# INC_ENC_IF.net
KiCad netlist of a schematic drawn in Altium Designer
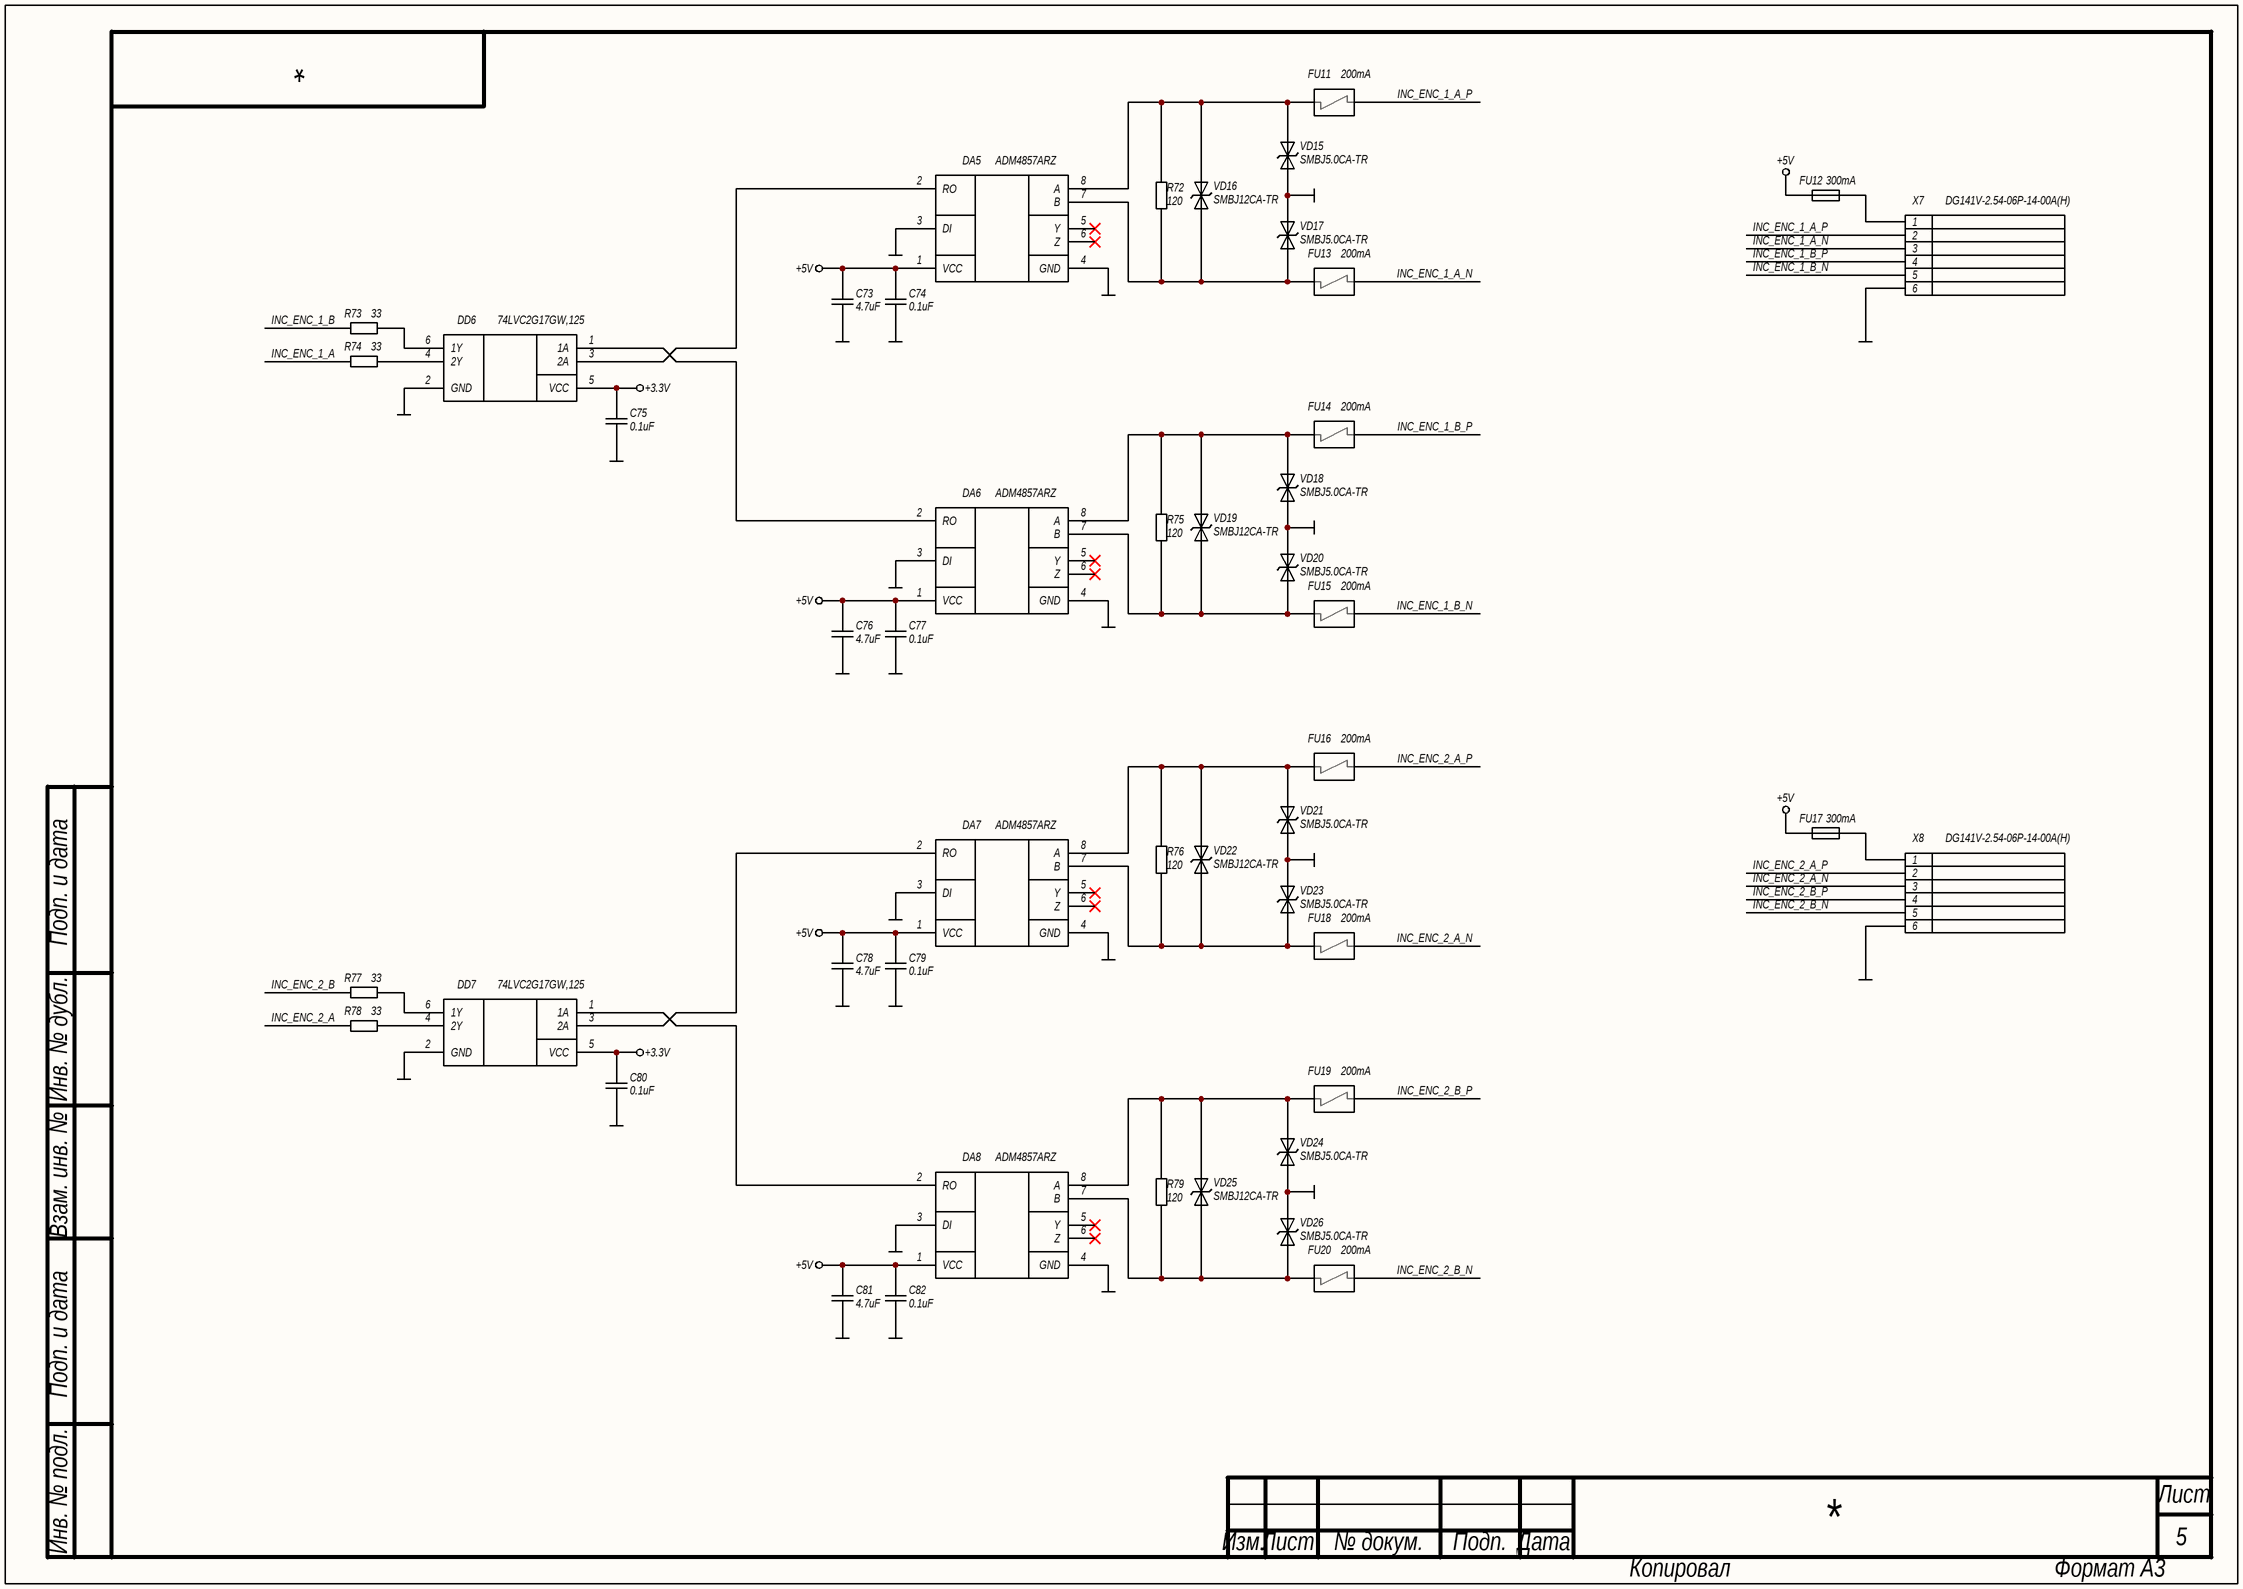
[diagram p0: INC_ENC_IF.SchDoc]

(export (version "E")
  (design (tool "Eeschema 10.0.6"))
  (components
    (comp (ref "C73")
      (value "4.7uF")
      (footprint "C0603N")
      (description "Конденсатор")
      (libsource (lib "Components Library") (part "CAP_FIXED"))
    )
    (comp (ref "C74")
      (value "0.1uF")
      (footprint "C0603N")
      (description "Конденсатор")
      (libsource (lib "Components Library") (part "CAP_FIXED"))
    )
    (comp (ref "C75")
      (value "0.1uF")
      (footprint "C0603N")
      (description "Конденсатор")
      (libsource (lib "Components Library") (part "CAP_FIXED"))
    )
    (comp (ref "C76")
      (value "4.7uF")
      (footprint "C0603N")
      (description "Конденсатор")
      (libsource (lib "Components Library") (part "CAP_FIXED"))
    )
    (comp (ref "C77")
      (value "0.1uF")
      (footprint "C0603N")
      (description "Конденсатор")
      (libsource (lib "Components Library") (part "CAP_FIXED"))
    )
    (comp (ref "C78")
      (value "4.7uF")
      (footprint "C0603N")
      (description "Конденсатор")
      (libsource (lib "Components Library") (part "CAP_FIXED"))
    )
    (comp (ref "C79")
      (value "0.1uF")
      (footprint "C0603N")
      (description "Конденсатор")
      (libsource (lib "Components Library") (part "CAP_FIXED"))
    )
    (comp (ref "C80")
      (value "0.1uF")
      (footprint "C0603N")
      (description "Конденсатор")
      (libsource (lib "Components Library") (part "CAP_FIXED"))
    )
    (comp (ref "C81")
      (value "4.7uF")
      (footprint "C0603N")
      (description "Конденсатор")
      (libsource (lib "Components Library") (part "CAP_FIXED"))
    )
    (comp (ref "C82")
      (value "0.1uF")
      (footprint "C0603N")
      (description "Конденсатор")
      (libsource (lib "Components Library") (part "CAP_FIXED"))
    )
    (comp (ref "DA5")
      (value "ADM4857ARZ")
      (footprint "SOIC8")
      (description "Микросхема интерфейса RS485")
      (libsource (lib "Components Library") (part "ADM4857A"))
    )
    (comp (ref "DA6")
      (value "ADM4857ARZ")
      (footprint "SOIC8")
      (description "Микросхема интерфейса RS485")
      (libsource (lib "Components Library") (part "ADM4857A"))
    )
    (comp (ref "DA7")
      (value "ADM4857ARZ")
      (footprint "SOIC8")
      (description "Микросхема интерфейса RS485")
      (libsource (lib "Components Library") (part "ADM4857A"))
    )
    (comp (ref "DA8")
      (value "ADM4857ARZ")
      (footprint "SOIC8")
      (description "Микросхема интерфейса RS485")
      (libsource (lib "Components Library") (part "ADM4857A"))
    )
    (comp (ref "DD6")
      (value "74LVC2G17GW,125")
      (footprint "SOT363-2")
      (description "Микросхема сдвоенный триггер Шмитта")
      (libsource (lib "Components Library") (part "74LVC2G17"))
    )
    (comp (ref "DD7")
      (value "74LVC2G17GW,125")
      (footprint "SOT363-2")
      (description "Микросхема сдвоенный триггер Шмитта")
      (libsource (lib "Components Library") (part "74LVC2G17"))
    )
    (comp (ref "FU11")
      (value "200mA")
      (footprint "TBU-CA")
      (description "Полупроводниковый предохранитель")
      (libsource (lib "Components Library") (part "FUSE_TBU"))
    )
    (comp (ref "FU12")
      (value "300mA")
      (footprint "MF-MSMF")
      (description "Плавкий предохранитель")
      (libsource (lib "Components Library") (part "FUSE"))
    )
    (comp (ref "FU13")
      (value "200mA")
      (footprint "TBU-CA")
      (description "Полупроводниковый предохранитель")
      (libsource (lib "Components Library") (part "FUSE_TBU"))
    )
    (comp (ref "FU14")
      (value "200mA")
      (footprint "TBU-CA")
      (description "Полупроводниковый предохранитель")
      (libsource (lib "Components Library") (part "FUSE_TBU"))
    )
    (comp (ref "FU15")
      (value "200mA")
      (footprint "TBU-CA")
      (description "Полупроводниковый предохранитель")
      (libsource (lib "Components Library") (part "FUSE_TBU"))
    )
    (comp (ref "FU16")
      (value "200mA")
      (footprint "TBU-CA")
      (description "Полупроводниковый предохранитель")
      (libsource (lib "Components Library") (part "FUSE_TBU"))
    )
    (comp (ref "FU17")
      (value "300mA")
      (footprint "MF-MSMF")
      (description "Плавкий предохранитель")
      (libsource (lib "Components Library") (part "FUSE"))
    )
    (comp (ref "FU18")
      (value "200mA")
      (footprint "TBU-CA")
      (description "Полупроводниковый предохранитель")
      (libsource (lib "Components Library") (part "FUSE_TBU"))
    )
    (comp (ref "FU19")
      (value "200mA")
      (footprint "TBU-CA")
      (description "Полупроводниковый предохранитель")
      (libsource (lib "Components Library") (part "FUSE_TBU"))
    )
    (comp (ref "FU20")
      (value "200mA")
      (footprint "TBU-CA")
      (description "Полупроводниковый предохранитель")
      (libsource (lib "Components Library") (part "FUSE_TBU"))
    )
    (comp (ref "R72")
      (value "120")
      (footprint "R0805N")
      (description "Резистор")
      (libsource (lib "") (part "RES_FIXED_1"))
    )
    (comp (ref "R73")
      (value "33")
      (footprint "R0603N")
      (description "Резистор")
      (libsource (lib "Components Library") (part "RES_FIXED"))
    )
    (comp (ref "R74")
      (value "33")
      (footprint "R0603N")
      (description "Резистор")
      (libsource (lib "Components Library") (part "RES_FIXED"))
    )
    (comp (ref "R75")
      (value "120")
      (footprint "R0805N")
      (description "Резистор")
      (libsource (lib "") (part "RES_FIXED_1"))
    )
    (comp (ref "R76")
      (value "120")
      (footprint "R0805N")
      (description "Резистор")
      (libsource (lib "") (part "RES_FIXED_1"))
    )
    (comp (ref "R77")
      (value "33")
      (footprint "R0603N")
      (description "Резистор")
      (libsource (lib "Components Library") (part "RES_FIXED"))
    )
    (comp (ref "R78")
      (value "33")
      (footprint "R0603N")
      (description "Резистор")
      (libsource (lib "Components Library") (part "RES_FIXED"))
    )
    (comp (ref "R79")
      (value "120")
      (footprint "R0805N")
      (description "Резистор")
      (libsource (lib "") (part "RES_FIXED_1"))
    )
    (comp (ref "VD15")
      (value "SMBJ5.0CA-TR")
      (footprint "SMB")
      (description "TVS диод двунаправленный")
      (libsource (lib "Components Library") (part "TVS_BIDIR"))
    )
    (comp (ref "VD16")
      (value "SMBJ12CA-TR")
      (footprint "SMB")
      (description "TVS диод двунаправленный")
      (libsource (lib "Components Library") (part "TVS_BIDIR"))
    )
    (comp (ref "VD17")
      (value "SMBJ5.0CA-TR")
      (footprint "SMB")
      (description "TVS диод двунаправленный")
      (libsource (lib "Components Library") (part "TVS_BIDIR"))
    )
    (comp (ref "VD18")
      (value "SMBJ5.0CA-TR")
      (footprint "SMB")
      (description "TVS диод двунаправленный")
      (libsource (lib "Components Library") (part "TVS_BIDIR"))
    )
    (comp (ref "VD19")
      (value "SMBJ12CA-TR")
      (footprint "SMB")
      (description "TVS диод двунаправленный")
      (libsource (lib "Components Library") (part "TVS_BIDIR"))
    )
    (comp (ref "VD20")
      (value "SMBJ5.0CA-TR")
      (footprint "SMB")
      (description "TVS диод двунаправленный")
      (libsource (lib "Components Library") (part "TVS_BIDIR"))
    )
    (comp (ref "VD21")
      (value "SMBJ5.0CA-TR")
      (footprint "SMB")
      (description "TVS диод двунаправленный")
      (libsource (lib "Components Library") (part "TVS_BIDIR"))
    )
    (comp (ref "VD22")
      (value "SMBJ12CA-TR")
      (footprint "SMB")
      (description "TVS диод двунаправленный")
      (libsource (lib "Components Library") (part "TVS_BIDIR"))
    )
    (comp (ref "VD23")
      (value "SMBJ5.0CA-TR")
      (footprint "SMB")
      (description "TVS диод двунаправленный")
      (libsource (lib "Components Library") (part "TVS_BIDIR"))
    )
    (comp (ref "VD24")
      (value "SMBJ5.0CA-TR")
      (footprint "SMB")
      (description "TVS диод двунаправленный")
      (libsource (lib "Components Library") (part "TVS_BIDIR"))
    )
    (comp (ref "VD25")
      (value "SMBJ12CA-TR")
      (footprint "SMB")
      (description "TVS диод двунаправленный")
      (libsource (lib "Components Library") (part "TVS_BIDIR"))
    )
    (comp (ref "VD26")
      (value "SMBJ5.0CA-TR")
      (footprint "SMB")
      (description "TVS диод двунаправленный")
      (libsource (lib "Components Library") (part "TVS_BIDIR"))
    )
    (comp (ref "X7")
      (value "DG141V-2.54-06P-14-00A(H)")
      (footprint "DG141V-2.54-06P-14-00A(H)")
      (description "Разъем, 6 контактов")
      (libsource (lib "Components Library") (part "Connector 6"))
    )
    (comp (ref "X8")
      (value "DG141V-2.54-06P-14-00A(H)")
      (footprint "DG141V-2.54-06P-14-00A(H)")
      (description "Разъем, 6 контактов")
      (libsource (lib "Components Library") (part "Connector 6"))
    )
  )
  (nets
    (net (code "1") (name "+3.3V") (class "Default")
      (node (ref "C75") (pin "2") (pinfunction "2_2") (pintype "passive"))
      (node (ref "C80") (pin "2") (pinfunction "2_2") (pintype "passive"))
      (node (ref "DD6") (pin "5") (pinfunction "VCC_5") (pintype "power_in"))
      (node (ref "DD7") (pin "5") (pinfunction "VCC_5") (pintype "power_in"))
    )
    (net (code "2") (name "+5V") (class "Default")
      (node (ref "C73") (pin "2") (pinfunction "2_2") (pintype "passive"))
      (node (ref "C74") (pin "2") (pinfunction "2_2") (pintype "passive"))
      (node (ref "C76") (pin "2") (pinfunction "2_2") (pintype "passive"))
      (node (ref "C77") (pin "2") (pinfunction "2_2") (pintype "passive"))
      (node (ref "C78") (pin "2") (pinfunction "2_2") (pintype "passive"))
      (node (ref "C79") (pin "2") (pinfunction "2_2") (pintype "passive"))
      (node (ref "C81") (pin "2") (pinfunction "2_2") (pintype "passive"))
      (node (ref "C82") (pin "2") (pinfunction "2_2") (pintype "passive"))
      (node (ref "DA5") (pin "1") (pinfunction "VCC_1") (pintype "power_in"))
      (node (ref "DA6") (pin "1") (pinfunction "VCC_1") (pintype "power_in"))
      (node (ref "DA7") (pin "1") (pinfunction "VCC_1") (pintype "power_in"))
      (node (ref "DA8") (pin "1") (pinfunction "VCC_1") (pintype "power_in"))
      (node (ref "FU12") (pin "1") (pinfunction "1_1") (pintype "passive"))
      (node (ref "FU17") (pin "1") (pinfunction "1_1") (pintype "passive"))
    )
    (net (code "3") (name "/INC_ENC_1_A") (class "Default")
      (node (ref "R74") (pin "2") (pinfunction "2_2") (pintype "passive"))
    )
    (net (code "4") (name "/INC_ENC_1_A_N") (class "Default")
      (node (ref "FU13") (pin "3") (pinfunction "IN/OUT_3") (pintype "passive"))
      (node (ref "X7") (pin "3") (pinfunction "3_3") (pintype "power_in"))
    )
    (net (code "5") (name "/INC_ENC_1_A_P") (class "Default")
      (node (ref "FU11") (pin "3") (pinfunction "IN/OUT_3") (pintype "passive"))
      (node (ref "X7") (pin "2") (pinfunction "2_2") (pintype "power_in"))
    )
    (net (code "6") (name "/INC_ENC_1_B") (class "Default")
      (node (ref "R73") (pin "2") (pinfunction "2_2") (pintype "passive"))
    )
    (net (code "7") (name "/INC_ENC_1_B_N") (class "Default")
      (node (ref "FU15") (pin "3") (pinfunction "IN/OUT_3") (pintype "passive"))
      (node (ref "X7") (pin "5") (pinfunction "5_5") (pintype "power_in"))
    )
    (net (code "8") (name "/INC_ENC_1_B_P") (class "Default")
      (node (ref "FU14") (pin "3") (pinfunction "IN/OUT_3") (pintype "passive"))
      (node (ref "X7") (pin "4") (pinfunction "4_4") (pintype "power_in"))
    )
    (net (code "9") (name "/INC_ENC_2_A") (class "Default")
      (node (ref "R78") (pin "2") (pinfunction "2_2") (pintype "passive"))
    )
    (net (code "10") (name "/INC_ENC_2_A_N") (class "Default")
      (node (ref "FU18") (pin "3") (pinfunction "IN/OUT_3") (pintype "passive"))
      (node (ref "X8") (pin "3") (pinfunction "3_3") (pintype "power_in"))
    )
    (net (code "11") (name "/INC_ENC_2_A_P") (class "Default")
      (node (ref "FU16") (pin "3") (pinfunction "IN/OUT_3") (pintype "passive"))
      (node (ref "X8") (pin "2") (pinfunction "2_2") (pintype "power_in"))
    )
    (net (code "12") (name "/INC_ENC_2_B") (class "Default")
      (node (ref "R77") (pin "2") (pinfunction "2_2") (pintype "passive"))
    )
    (net (code "13") (name "/INC_ENC_2_B_N") (class "Default")
      (node (ref "FU20") (pin "3") (pinfunction "IN/OUT_3") (pintype "passive"))
      (node (ref "X8") (pin "5") (pinfunction "5_5") (pintype "power_in"))
    )
    (net (code "14") (name "/INC_ENC_2_B_P") (class "Default")
      (node (ref "FU19") (pin "3") (pinfunction "IN/OUT_3") (pintype "passive"))
      (node (ref "X8") (pin "4") (pinfunction "4_4") (pintype "power_in"))
    )
    (net (code "15") (name "GND") (class "Default")
      (node (ref "C73") (pin "1") (pinfunction "1_1") (pintype "passive"))
      (node (ref "C74") (pin "1") (pinfunction "1_1") (pintype "passive"))
      (node (ref "C75") (pin "1") (pinfunction "1_1") (pintype "passive"))
      (node (ref "C76") (pin "1") (pinfunction "1_1") (pintype "passive"))
      (node (ref "C77") (pin "1") (pinfunction "1_1") (pintype "passive"))
      (node (ref "C78") (pin "1") (pinfunction "1_1") (pintype "passive"))
      (node (ref "C79") (pin "1") (pinfunction "1_1") (pintype "passive"))
      (node (ref "C80") (pin "1") (pinfunction "1_1") (pintype "passive"))
      (node (ref "C81") (pin "1") (pinfunction "1_1") (pintype "passive"))
      (node (ref "C82") (pin "1") (pinfunction "1_1") (pintype "passive"))
      (node (ref "DA5") (pin "3") (pinfunction "DI_3") (pintype "power_in"))
      (node (ref "DA5") (pin "4") (pinfunction "GND_4") (pintype "power_in"))
      (node (ref "DA6") (pin "3") (pinfunction "DI_3") (pintype "power_in"))
      (node (ref "DA6") (pin "4") (pinfunction "GND_4") (pintype "power_in"))
      (node (ref "DA7") (pin "3") (pinfunction "DI_3") (pintype "power_in"))
      (node (ref "DA7") (pin "4") (pinfunction "GND_4") (pintype "power_in"))
      (node (ref "DA8") (pin "3") (pinfunction "DI_3") (pintype "power_in"))
      (node (ref "DA8") (pin "4") (pinfunction "GND_4") (pintype "power_in"))
      (node (ref "DD6") (pin "2") (pinfunction "GND_2") (pintype "power_in"))
      (node (ref "DD7") (pin "2") (pinfunction "GND_2") (pintype "power_in"))
      (node (ref "VD15") (pin "2") (pinfunction "A2_2") (pintype "passive"))
      (node (ref "VD17") (pin "2") (pinfunction "A2_2") (pintype "passive"))
      (node (ref "VD18") (pin "2") (pinfunction "A2_2") (pintype "passive"))
      (node (ref "VD20") (pin "2") (pinfunction "A2_2") (pintype "passive"))
      (node (ref "VD21") (pin "2") (pinfunction "A2_2") (pintype "passive"))
      (node (ref "VD23") (pin "2") (pinfunction "A2_2") (pintype "passive"))
      (node (ref "VD24") (pin "2") (pinfunction "A2_2") (pintype "passive"))
      (node (ref "VD26") (pin "2") (pinfunction "A2_2") (pintype "passive"))
      (node (ref "X7") (pin "6") (pinfunction "6_6") (pintype "power_in"))
      (node (ref "X8") (pin "6") (pinfunction "6_6") (pintype "power_in"))
    )
    (net (code "16") (name "Net-(DA5-A)") (class "Default")
      (node (ref "DA5") (pin "8") (pinfunction "A_8") (pintype "power_in"))
      (node (ref "FU11") (pin "1") (pinfunction "IN/OUT_1") (pintype "passive"))
      (node (ref "R72") (pin "1") (pinfunction "1_1") (pintype "passive"))
      (node (ref "VD15") (pin "1") (pinfunction "A1_1") (pintype "passive"))
      (node (ref "VD16") (pin "1") (pinfunction "A1_1") (pintype "passive"))
    )
    (net (code "17") (name "Net-(DA5-B)") (class "Default")
      (node (ref "DA5") (pin "7") (pinfunction "B_7") (pintype "power_in"))
      (node (ref "FU13") (pin "1") (pinfunction "IN/OUT_1") (pintype "passive"))
      (node (ref "R72") (pin "2") (pinfunction "2_2") (pintype "passive"))
      (node (ref "VD16") (pin "2") (pinfunction "A2_2") (pintype "passive"))
      (node (ref "VD17") (pin "1") (pinfunction "A1_1") (pintype "passive"))
    )
    (net (code "18") (name "Net-(DA5-RO)") (class "Default")
      (node (ref "DA5") (pin "2") (pinfunction "RO_2") (pintype "power_in"))
      (node (ref "DD6") (pin "3") (pinfunction "2A_3") (pintype "power_in"))
    )
    (net (code "19") (name "Net-(DA6-A)") (class "Default")
      (node (ref "DA6") (pin "8") (pinfunction "A_8") (pintype "power_in"))
      (node (ref "FU14") (pin "1") (pinfunction "IN/OUT_1") (pintype "passive"))
      (node (ref "R75") (pin "1") (pinfunction "1_1") (pintype "passive"))
      (node (ref "VD18") (pin "1") (pinfunction "A1_1") (pintype "passive"))
      (node (ref "VD19") (pin "1") (pinfunction "A1_1") (pintype "passive"))
    )
    (net (code "20") (name "Net-(DA6-B)") (class "Default")
      (node (ref "DA6") (pin "7") (pinfunction "B_7") (pintype "power_in"))
      (node (ref "FU15") (pin "1") (pinfunction "IN/OUT_1") (pintype "passive"))
      (node (ref "R75") (pin "2") (pinfunction "2_2") (pintype "passive"))
      (node (ref "VD19") (pin "2") (pinfunction "A2_2") (pintype "passive"))
      (node (ref "VD20") (pin "1") (pinfunction "A1_1") (pintype "passive"))
    )
    (net (code "21") (name "Net-(DA6-RO)") (class "Default")
      (node (ref "DA6") (pin "2") (pinfunction "RO_2") (pintype "power_in"))
      (node (ref "DD6") (pin "1") (pinfunction "1A_1") (pintype "power_in"))
    )
    (net (code "22") (name "Net-(DA7-A)") (class "Default")
      (node (ref "DA7") (pin "8") (pinfunction "A_8") (pintype "power_in"))
      (node (ref "FU16") (pin "1") (pinfunction "IN/OUT_1") (pintype "passive"))
      (node (ref "R76") (pin "1") (pinfunction "1_1") (pintype "passive"))
      (node (ref "VD21") (pin "1") (pinfunction "A1_1") (pintype "passive"))
      (node (ref "VD22") (pin "1") (pinfunction "A1_1") (pintype "passive"))
    )
    (net (code "23") (name "Net-(DA7-B)") (class "Default")
      (node (ref "DA7") (pin "7") (pinfunction "B_7") (pintype "power_in"))
      (node (ref "FU18") (pin "1") (pinfunction "IN/OUT_1") (pintype "passive"))
      (node (ref "R76") (pin "2") (pinfunction "2_2") (pintype "passive"))
      (node (ref "VD22") (pin "2") (pinfunction "A2_2") (pintype "passive"))
      (node (ref "VD23") (pin "1") (pinfunction "A1_1") (pintype "passive"))
    )
    (net (code "24") (name "Net-(DA7-RO)") (class "Default")
      (node (ref "DA7") (pin "2") (pinfunction "RO_2") (pintype "power_in"))
      (node (ref "DD7") (pin "3") (pinfunction "2A_3") (pintype "power_in"))
    )
    (net (code "25") (name "Net-(DA8-A)") (class "Default")
      (node (ref "DA8") (pin "8") (pinfunction "A_8") (pintype "power_in"))
      (node (ref "FU19") (pin "1") (pinfunction "IN/OUT_1") (pintype "passive"))
      (node (ref "R79") (pin "1") (pinfunction "1_1") (pintype "passive"))
      (node (ref "VD24") (pin "1") (pinfunction "A1_1") (pintype "passive"))
      (node (ref "VD25") (pin "1") (pinfunction "A1_1") (pintype "passive"))
    )
    (net (code "26") (name "Net-(DA8-B)") (class "Default")
      (node (ref "DA8") (pin "7") (pinfunction "B_7") (pintype "power_in"))
      (node (ref "FU20") (pin "1") (pinfunction "IN/OUT_1") (pintype "passive"))
      (node (ref "R79") (pin "2") (pinfunction "2_2") (pintype "passive"))
      (node (ref "VD25") (pin "2") (pinfunction "A2_2") (pintype "passive"))
      (node (ref "VD26") (pin "1") (pinfunction "A1_1") (pintype "passive"))
    )
    (net (code "27") (name "Net-(DA8-RO)") (class "Default")
      (node (ref "DA8") (pin "2") (pinfunction "RO_2") (pintype "power_in"))
      (node (ref "DD7") (pin "1") (pinfunction "1A_1") (pintype "power_in"))
    )
    (net (code "28") (name "Net-(DD6-1Y)") (class "Default")
      (node (ref "DD6") (pin "6") (pinfunction "1Y_6") (pintype "power_in"))
      (node (ref "R73") (pin "1") (pinfunction "1_1") (pintype "passive"))
    )
    (net (code "29") (name "Net-(DD6-2Y)") (class "Default")
      (node (ref "DD6") (pin "4") (pinfunction "2Y_4") (pintype "power_in"))
      (node (ref "R74") (pin "1") (pinfunction "1_1") (pintype "passive"))
    )
    (net (code "30") (name "Net-(DD7-1Y)") (class "Default")
      (node (ref "DD7") (pin "6") (pinfunction "1Y_6") (pintype "power_in"))
      (node (ref "R77") (pin "1") (pinfunction "1_1") (pintype "passive"))
    )
    (net (code "31") (name "Net-(DD7-2Y)") (class "Default")
      (node (ref "DD7") (pin "4") (pinfunction "2Y_4") (pintype "power_in"))
      (node (ref "R78") (pin "1") (pinfunction "1_1") (pintype "passive"))
    )
    (net (code "32") (name "Net-(FU12-Pad2)") (class "Default")
      (node (ref "FU12") (pin "2") (pinfunction "2_2") (pintype "passive"))
      (node (ref "X7") (pin "1") (pinfunction "1_1") (pintype "power_in"))
    )
    (net (code "33") (name "Net-(FU17-Pad2)") (class "Default")
      (node (ref "FU17") (pin "2") (pinfunction "2_2") (pintype "passive"))
      (node (ref "X8") (pin "1") (pinfunction "1_1") (pintype "power_in"))
    )
    (net (code "34") (name "unconnected-(DA5-Y-Pad5)") (class "Default")
      (node (ref "DA5") (pin "5") (pinfunction "Y_5") (pintype "power_in+no_connect"))
    )
    (net (code "35") (name "unconnected-(DA5-Z-Pad6)") (class "Default")
      (node (ref "DA5") (pin "6") (pinfunction "Z_6") (pintype "power_in+no_connect"))
    )
    (net (code "36") (name "unconnected-(DA6-Y-Pad5)") (class "Default")
      (node (ref "DA6") (pin "5") (pinfunction "Y_5") (pintype "power_in+no_connect"))
    )
    (net (code "37") (name "unconnected-(DA6-Z-Pad6)") (class "Default")
      (node (ref "DA6") (pin "6") (pinfunction "Z_6") (pintype "power_in+no_connect"))
    )
    (net (code "38") (name "unconnected-(DA7-Y-Pad5)") (class "Default")
      (node (ref "DA7") (pin "5") (pinfunction "Y_5") (pintype "power_in+no_connect"))
    )
    (net (code "39") (name "unconnected-(DA7-Z-Pad6)") (class "Default")
      (node (ref "DA7") (pin "6") (pinfunction "Z_6") (pintype "power_in+no_connect"))
    )
    (net (code "40") (name "unconnected-(DA8-Y-Pad5)") (class "Default")
      (node (ref "DA8") (pin "5") (pinfunction "Y_5") (pintype "power_in+no_connect"))
    )
    (net (code "41") (name "unconnected-(DA8-Z-Pad6)") (class "Default")
      (node (ref "DA8") (pin "6") (pinfunction "Z_6") (pintype "power_in+no_connect"))
    )
  )
)
